# Quad-RS232-1_0-TTL.net
KiCad netlist of a schematic drawn in Altium Designer
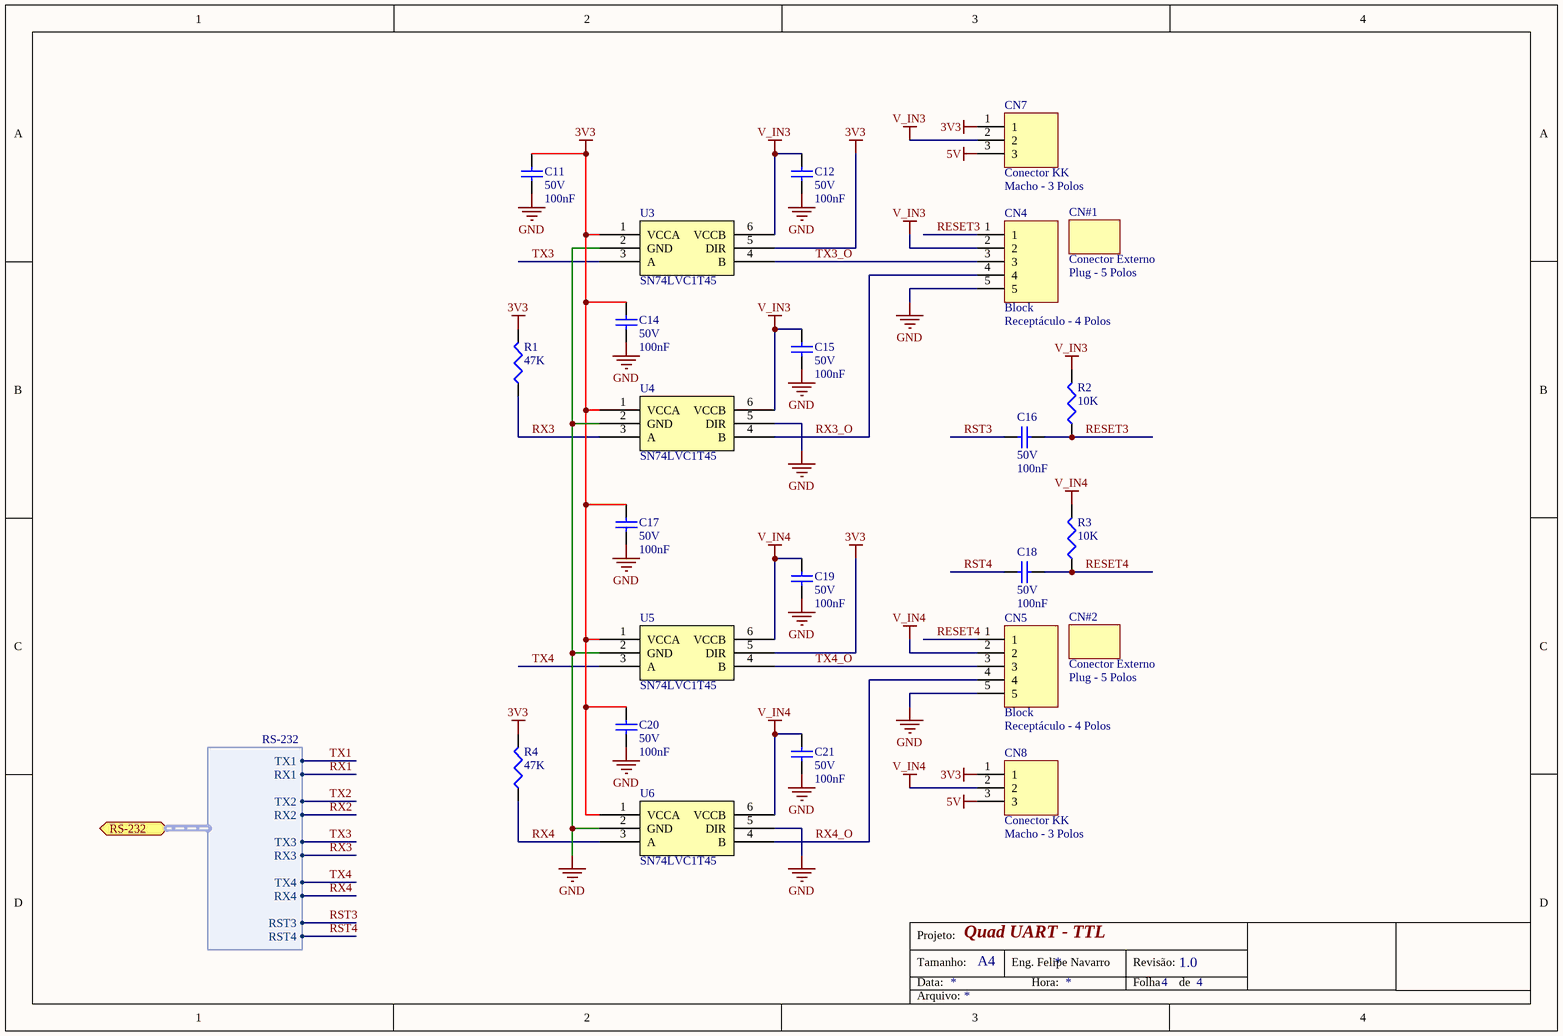
[diagram p0: Quad-RS232-1.0-TTL.SchDoc]

(export (version "E")
  (design (tool "Eeschema 10.0.6"))
  (components
    (comp (ref "C11")
      (value "100nF")
      (footprint "CC0603")
      (description "Capacitor (Semiconductor SIM Model)")
      (fields (field (name "TENSÃO") "50V") (field (name "Comment") "Capacitor Cerâmico"))
      (libsource (lib "NavarroCAP") (part "Cap 100nF 50V 0603 X7R"))
    )
    (comp (ref "C12")
      (value "100nF")
      (footprint "CC0603")
      (description "Capacitor (Semiconductor SIM Model)")
      (fields (field (name "TENSÃO") "50V") (field (name "Comment") "Capacitor Cerâmico"))
      (libsource (lib "NavarroCAP") (part "Cap 100nF 50V 0603 X7R"))
    )
    (comp (ref "C14")
      (value "100nF")
      (footprint "CC0603")
      (description "Capacitor (Semiconductor SIM Model)")
      (fields (field (name "TENSÃO") "50V") (field (name "Comment") "Capacitor Cerâmico"))
      (libsource (lib "NavarroCAP") (part "Cap 100nF 50V 0603 X7R"))
    )
    (comp (ref "C15")
      (value "100nF")
      (footprint "CC0603")
      (description "Capacitor (Semiconductor SIM Model)")
      (fields (field (name "TENSÃO") "50V") (field (name "Comment") "Capacitor Cerâmico"))
      (libsource (lib "NavarroCAP") (part "Cap 100nF 50V 0603 X7R"))
    )
    (comp (ref "C16")
      (value "100nF")
      (footprint "CC0603")
      (description "Capacitor (Semiconductor SIM Model)")
      (fields (field (name "TENSÃO") "50V") (field (name "Comment") "Capacitor Cerâmico"))
      (libsource (lib "NavarroCAP") (part "Cap 100nF 50V 0603 X7R"))
    )
    (comp (ref "C17")
      (value "100nF")
      (footprint "CC0603")
      (description "Capacitor (Semiconductor SIM Model)")
      (fields (field (name "TENSÃO") "50V") (field (name "Comment") "Capacitor Cerâmico"))
      (libsource (lib "NavarroCAP") (part "Cap 100nF 50V 0603 X7R"))
    )
    (comp (ref "C18")
      (value "100nF")
      (footprint "CC0603")
      (description "Capacitor (Semiconductor SIM Model)")
      (fields (field (name "TENSÃO") "50V") (field (name "Comment") "Capacitor Cerâmico"))
      (libsource (lib "NavarroCAP") (part "Cap 100nF 50V 0603 X7R"))
    )
    (comp (ref "C19")
      (value "100nF")
      (footprint "CC0603")
      (description "Capacitor (Semiconductor SIM Model)")
      (fields (field (name "TENSÃO") "50V") (field (name "Comment") "Capacitor Cerâmico"))
      (libsource (lib "NavarroCAP") (part "Cap 100nF 50V 0603 X7R"))
    )
    (comp (ref "C20")
      (value "100nF")
      (footprint "CC0603")
      (description "Capacitor (Semiconductor SIM Model)")
      (fields (field (name "TENSÃO") "50V") (field (name "Comment") "Capacitor Cerâmico"))
      (libsource (lib "NavarroCAP") (part "Cap 100nF 50V 0603 X7R"))
    )
    (comp (ref "C21")
      (value "100nF")
      (footprint "CC0603")
      (description "Capacitor (Semiconductor SIM Model)")
      (fields (field (name "TENSÃO") "50V") (field (name "Comment") "Capacitor Cerâmico"))
      (libsource (lib "NavarroCAP") (part "Cap 100nF 50V 0603 X7R"))
    )
    (comp (ref "CN#1")
      (value "Conector Externo")
      (footprint "N/A")
      (description "Conector Plug")
      (fields (field (name "ALTIUM_VALUE") "Plug - 5 Polos"))
      (libsource (lib "NavarroCON") (part "Plug Block 5P 3.81mm"))
    )
    (comp (ref "CN#2")
      (value "Conector Externo")
      (footprint "N/A")
      (description "Conector Plug")
      (fields (field (name "ALTIUM_VALUE") "Plug - 5 Polos"))
      (libsource (lib "NavarroCON") (part "Plug Block 5P 3.81mm"))
    )
    (comp (ref "CN4")
      (value "Block")
      (footprint "CONN BLOCK5 RCPT/H 3.81")
      (description "Conector Shrouded Block")
      (fields (field (name "ALTIUM_VALUE") "Receptáculo - 4 Polos"))
      (libsource (lib "NavarroCON") (part "SHRD Block 5P RCPT-H P3.81mm"))
    )
    (comp (ref "CN5")
      (value "Block")
      (footprint "CONN BLOCK5 RCPT/H 3.81")
      (description "Conector Shrouded Block")
      (fields (field (name "ALTIUM_VALUE") "Receptáculo - 4 Polos"))
      (libsource (lib "NavarroCON") (part "SHRD Block 5P RCPT-H P3.81mm"))
    )
    (comp (ref "CN7")
      (value "Conector KK")
      (footprint "CONN HDR3-POL P.100 - H")
      (fields (field (name "ALTIUM_VALUE") "Macho - 3 Polos"))
      (libsource (lib "NavarroCON") (part "KK 3P Macho-H P2.54mm"))
    )
    (comp (ref "CN8")
      (value "Conector KK")
      (footprint "CONN HDR3-POL P.100 - H")
      (fields (field (name "ALTIUM_VALUE") "Macho - 3 Polos"))
      (libsource (lib "NavarroCON") (part "KK 3P Macho-H P2.54mm"))
    )
    (comp (ref "R1")
      (value "47K")
      (footprint "CC0603")
      (description "Resistor")
      (libsource (lib "NavarroRES") (part "Res 47K 1% 0603 1/10W"))
    )
    (comp (ref "R2")
      (value "10K")
      (footprint "CC0603")
      (description "Resistor")
      (libsource (lib "NavarroRES") (part "Res 10K 1% 0603 1/10W"))
    )
    (comp (ref "R3")
      (value "10K")
      (footprint "CC0603")
      (description "Resistor")
      (libsource (lib "NavarroRES") (part "Res 10K 1% 0603 1/10W"))
    )
    (comp (ref "R4")
      (value "47K")
      (footprint "CC0603")
      (description "Resistor")
      (libsource (lib "NavarroRES") (part "Res 47K 1% 0603 1/10W"))
    )
    (comp (ref "U3")
      (value "SN74LVC1T45")
      (footprint "SOT-23-6N")
      (description "SINGLE-BIT DUAL-SUPPLY BUS TRANSCEIVER  WITH CONFIGURABLE VOLTAGE TRANSLATION AND 3-STATE OUTPUTS")
      (libsource (lib "Navarro") (part "SN74LVC1T45"))
    )
    (comp (ref "U4")
      (value "SN74LVC1T45")
      (footprint "SOT-23-6N")
      (description "SINGLE-BIT DUAL-SUPPLY BUS TRANSCEIVER  WITH CONFIGURABLE VOLTAGE TRANSLATION AND 3-STATE OUTPUTS")
      (libsource (lib "Navarro") (part "SN74LVC1T45"))
    )
    (comp (ref "U5")
      (value "SN74LVC1T45")
      (footprint "SOT-23-6N")
      (description "SINGLE-BIT DUAL-SUPPLY BUS TRANSCEIVER  WITH CONFIGURABLE VOLTAGE TRANSLATION AND 3-STATE OUTPUTS")
      (libsource (lib "Navarro") (part "SN74LVC1T45"))
    )
    (comp (ref "U6")
      (value "SN74LVC1T45")
      (footprint "SOT-23-6N")
      (description "SINGLE-BIT DUAL-SUPPLY BUS TRANSCEIVER  WITH CONFIGURABLE VOLTAGE TRANSLATION AND 3-STATE OUTPUTS")
      (libsource (lib "Navarro") (part "SN74LVC1T45"))
    )
  )
  (nets
    (net (code "2") (name "/RESET3") (class "Default")
      (node (ref "C16") (pin "2") (pinfunction "2_2") (pintype "passive"))
      (node (ref "CN4") (pin "1") (pinfunction "1_1") (pintype "passive"))
      (node (ref "R2") (pin "1") (pinfunction "1_1") (pintype "passive"))
    )
    (net (code "3") (name "/RESET4") (class "Default")
      (node (ref "C18") (pin "2") (pinfunction "2_2") (pintype "passive"))
      (node (ref "CN5") (pin "1") (pinfunction "1_1") (pintype "passive"))
      (node (ref "R3") (pin "1") (pinfunction "1_1") (pintype "passive"))
    )
    (net (code "4") (name "/RST3") (class "Default")
      (node (ref "C16") (pin "1") (pinfunction "1_1") (pintype "passive"))
    )
    (net (code "5") (name "/RST4") (class "Default")
      (node (ref "C18") (pin "1") (pinfunction "1_1") (pintype "passive"))
    )
    (net (code "8") (name "/RX3") (class "Default")
      (node (ref "R1") (pin "1") (pinfunction "1_1") (pintype "passive"))
      (node (ref "U4") (pin "3") (pinfunction "A_3") (pintype "passive"))
    )
    (net (code "9") (name "/RX3_O") (class "Default")
      (node (ref "CN4") (pin "4") (pinfunction "4_4") (pintype "passive"))
      (node (ref "U4") (pin "4") (pinfunction "B_4") (pintype "passive"))
    )
    (net (code "10") (name "/RX4") (class "Default")
      (node (ref "R4") (pin "1") (pinfunction "1_1") (pintype "passive"))
      (node (ref "U6") (pin "3") (pinfunction "A_3") (pintype "passive"))
    )
    (net (code "11") (name "/RX4_O") (class "Default")
      (node (ref "CN5") (pin "4") (pinfunction "4_4") (pintype "passive"))
      (node (ref "U6") (pin "4") (pinfunction "B_4") (pintype "passive"))
    )
    (net (code "14") (name "/TX3") (class "Default")
      (node (ref "U3") (pin "3") (pinfunction "A_3") (pintype "passive"))
    )
    (net (code "15") (name "/TX3_O") (class "Default")
      (node (ref "CN4") (pin "3") (pinfunction "3_3") (pintype "passive"))
      (node (ref "U3") (pin "4") (pinfunction "B_4") (pintype "passive"))
    )
    (net (code "16") (name "/TX4") (class "Default")
      (node (ref "U5") (pin "3") (pinfunction "A_3") (pintype "passive"))
    )
    (net (code "17") (name "/TX4_O") (class "Default")
      (node (ref "CN5") (pin "3") (pinfunction "3_3") (pintype "passive"))
      (node (ref "U5") (pin "4") (pinfunction "B_4") (pintype "passive"))
    )
    (net (code "19") (name "3V3") (class "Default")
      (node (ref "C11") (pin "2") (pinfunction "2_2") (pintype "passive"))
      (node (ref "C14") (pin "2") (pinfunction "2_2") (pintype "passive"))
      (node (ref "C17") (pin "2") (pinfunction "2_2") (pintype "passive"))
      (node (ref "C20") (pin "2") (pinfunction "2_2") (pintype "passive"))
      (node (ref "CN7") (pin "1") (pinfunction "1_1") (pintype "passive"))
      (node (ref "CN8") (pin "1") (pinfunction "1_1") (pintype "passive"))
      (node (ref "R1") (pin "2") (pinfunction "2_2") (pintype "passive"))
      (node (ref "R4") (pin "2") (pinfunction "2_2") (pintype "passive"))
      (node (ref "U3") (pin "1") (pinfunction "VCCA_1") (pintype "passive"))
      (node (ref "U3") (pin "5") (pinfunction "DIR_5") (pintype "passive"))
      (node (ref "U4") (pin "1") (pinfunction "VCCA_1") (pintype "passive"))
      (node (ref "U5") (pin "1") (pinfunction "VCCA_1") (pintype "passive"))
      (node (ref "U5") (pin "5") (pinfunction "DIR_5") (pintype "passive"))
      (node (ref "U6") (pin "1") (pinfunction "VCCA_1") (pintype "passive"))
    )
    (net (code "20") (name "5V") (class "Default")
      (node (ref "CN7") (pin "3") (pinfunction "3_3") (pintype "passive"))
      (node (ref "CN8") (pin "3") (pinfunction "3_3") (pintype "passive"))
    )
    (net (code "21") (name "GND") (class "Default")
      (node (ref "C11") (pin "1") (pinfunction "1_1") (pintype "passive"))
      (node (ref "C12") (pin "1") (pinfunction "1_1") (pintype "passive"))
      (node (ref "C14") (pin "1") (pinfunction "1_1") (pintype "passive"))
      (node (ref "C15") (pin "1") (pinfunction "1_1") (pintype "passive"))
      (node (ref "C17") (pin "1") (pinfunction "1_1") (pintype "passive"))
      (node (ref "C19") (pin "1") (pinfunction "1_1") (pintype "passive"))
      (node (ref "C20") (pin "1") (pinfunction "1_1") (pintype "passive"))
      (node (ref "C21") (pin "1") (pinfunction "1_1") (pintype "passive"))
      (node (ref "CN4") (pin "5") (pinfunction "5_5") (pintype "passive"))
      (node (ref "CN5") (pin "5") (pinfunction "5_5") (pintype "passive"))
      (node (ref "U3") (pin "2") (pinfunction "GND_2") (pintype "passive"))
      (node (ref "U4") (pin "2") (pinfunction "GND_2") (pintype "passive"))
      (node (ref "U4") (pin "5") (pinfunction "DIR_5") (pintype "passive"))
      (node (ref "U5") (pin "2") (pinfunction "GND_2") (pintype "passive"))
      (node (ref "U6") (pin "2") (pinfunction "GND_2") (pintype "passive"))
      (node (ref "U6") (pin "5") (pinfunction "DIR_5") (pintype "passive"))
    )
    (net (code "22") (name "V_IN3") (class "Default")
      (node (ref "C12") (pin "2") (pinfunction "2_2") (pintype "passive"))
      (node (ref "C15") (pin "2") (pinfunction "2_2") (pintype "passive"))
      (node (ref "CN4") (pin "2") (pinfunction "2_2") (pintype "passive"))
      (node (ref "CN7") (pin "2") (pinfunction "2_2") (pintype "passive"))
      (node (ref "R2") (pin "2") (pinfunction "2_2") (pintype "passive"))
      (node (ref "U3") (pin "6") (pinfunction "VCCB_6") (pintype "passive"))
      (node (ref "U4") (pin "6") (pinfunction "VCCB_6") (pintype "passive"))
    )
    (net (code "23") (name "V_IN4") (class "Default")
      (node (ref "C19") (pin "2") (pinfunction "2_2") (pintype "passive"))
      (node (ref "C21") (pin "2") (pinfunction "2_2") (pintype "passive"))
      (node (ref "CN5") (pin "2") (pinfunction "2_2") (pintype "passive"))
      (node (ref "CN8") (pin "2") (pinfunction "2_2") (pintype "passive"))
      (node (ref "R3") (pin "2") (pinfunction "2_2") (pintype "passive"))
      (node (ref "U5") (pin "6") (pinfunction "VCCB_6") (pintype "passive"))
      (node (ref "U6") (pin "6") (pinfunction "VCCB_6") (pintype "passive"))
    )
  )
)
